# Faceplate_Display.net
KiCad netlist of a schematic drawn in Altium Designer
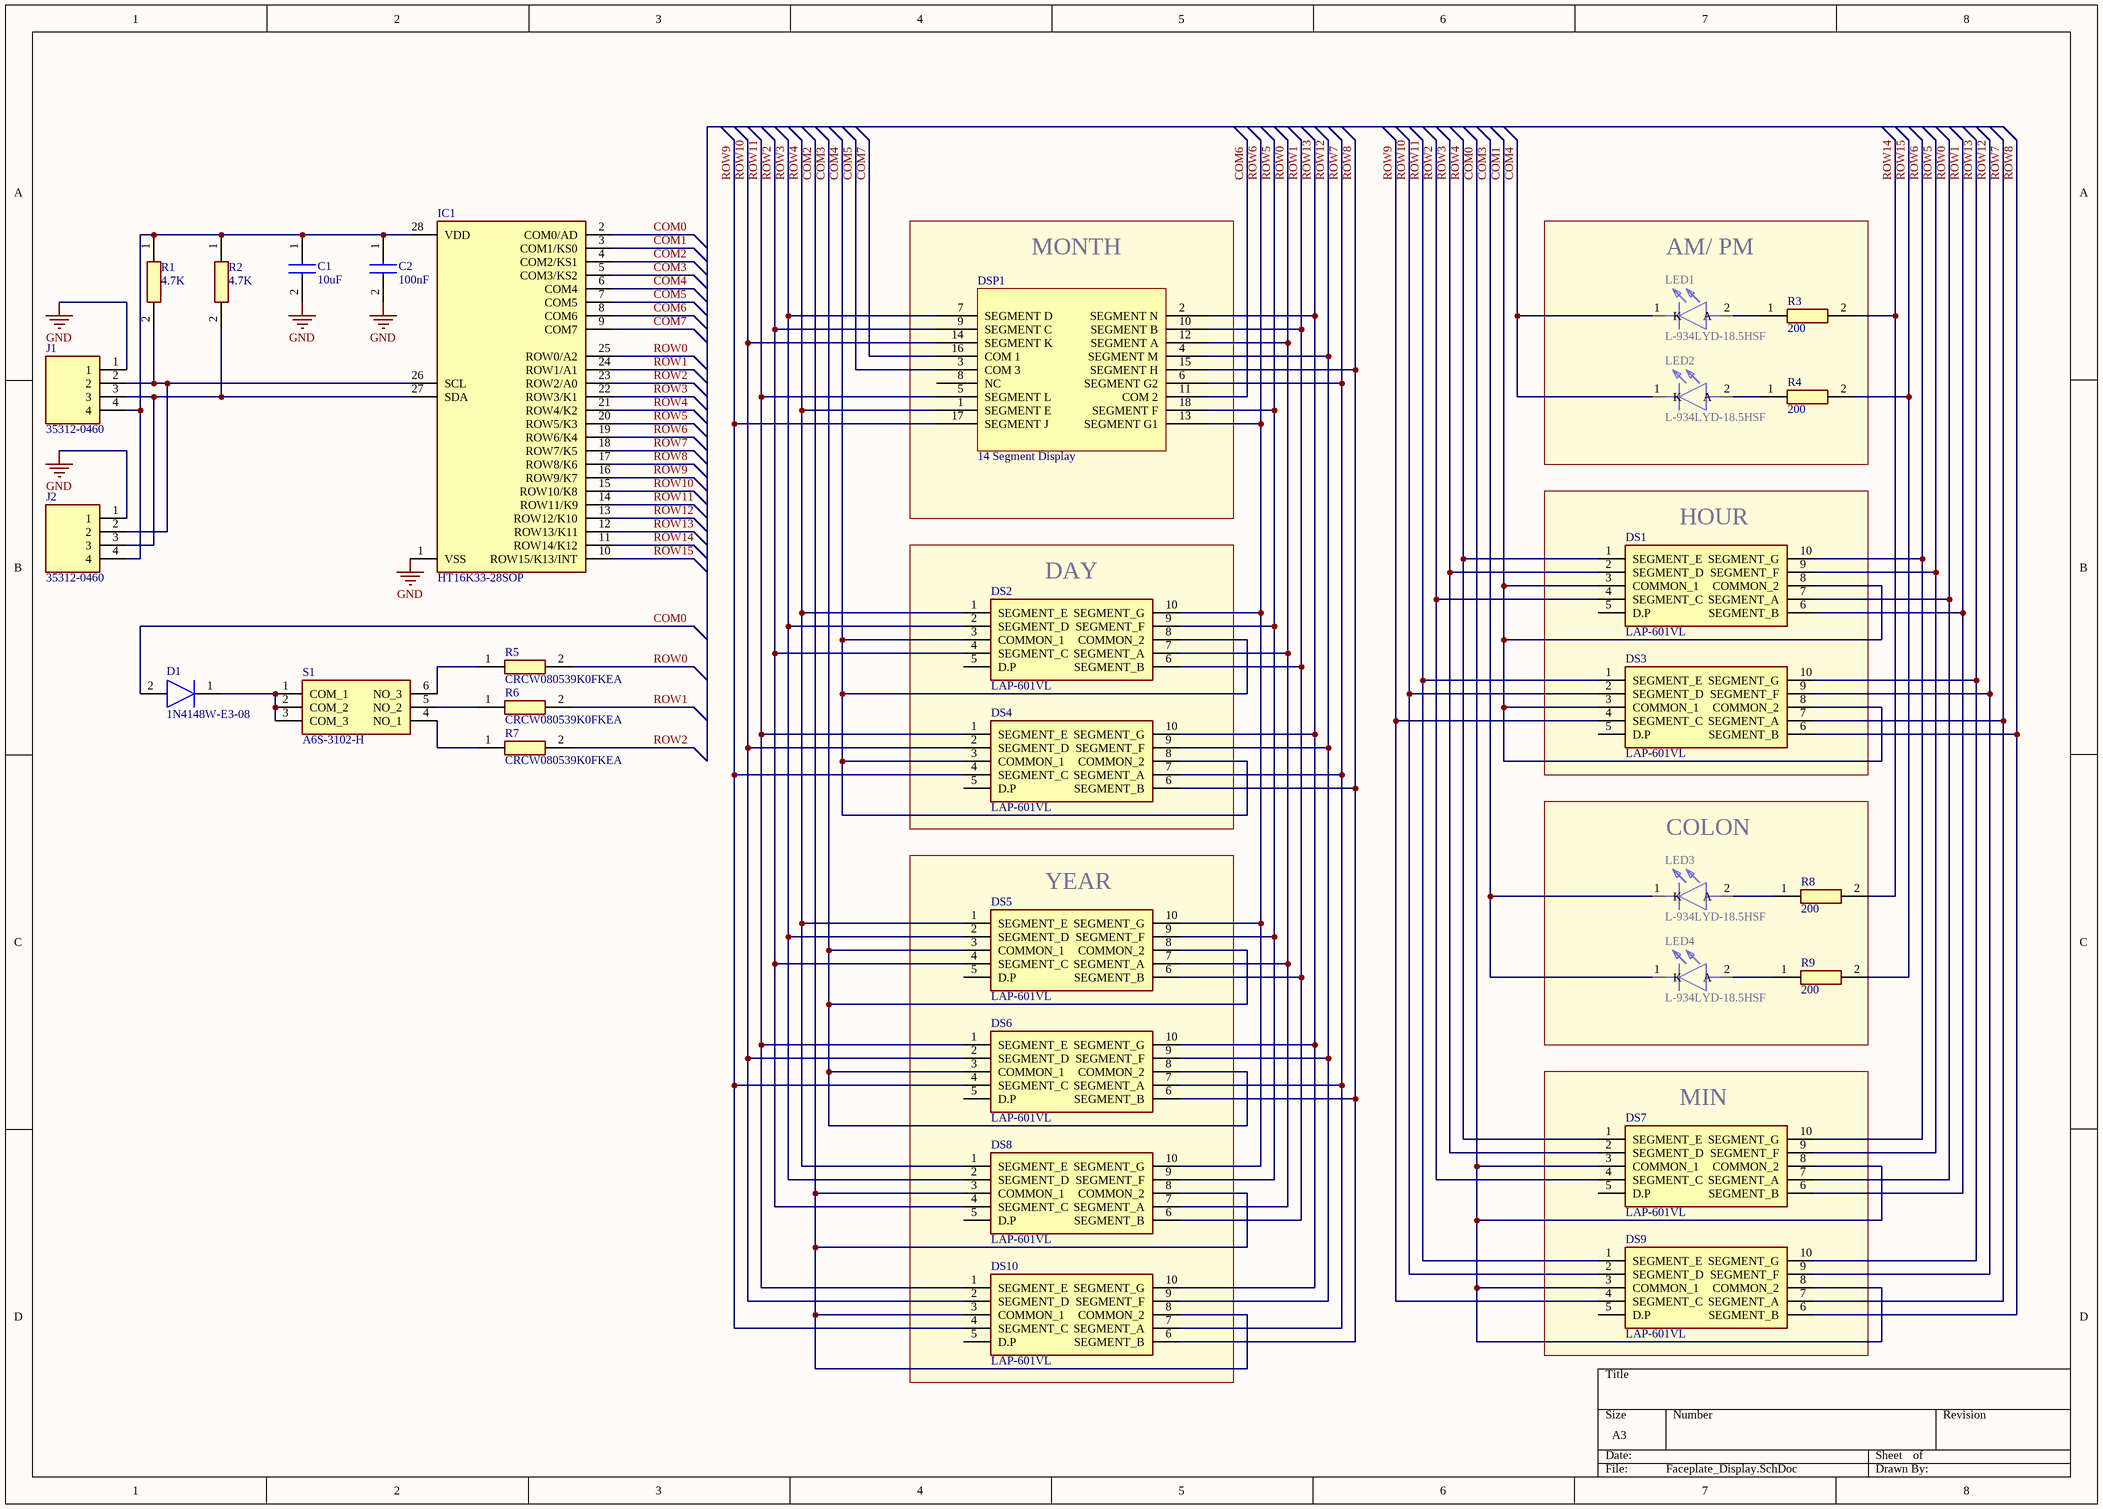
[diagram p0: Faceplate_Display.SchDoc]

(export (version "E")
  (design (tool "Eeschema 10.0.6"))
  (components
    (comp (ref "C1")
      (value "10uF")
      (footprint "SamacSys:CAPC2012X145N")
      (description "Capacitor")
      (fields
        (field (name "MANUFACTURER_PART_NUMBER") "VJ0805Y104KXAAT")
        (field (name "MOUSER PART NUMBER") "77-VJ0805Y104KXAAT")
      )
      (libsource (lib "*") (part "VJ0805Y104KXAAT"))
    )
    (comp (ref "C2")
      (value "100nF")
      (footprint "SamacSys:CAPC2012X88N")
      (description "Capacitor")
      (fields
        (field (name "MANUFACTURER_PART_NUMBER") "C0805C104K4RACTU")
        (field (name "MOUSER PART NUMBER") "80-C0805C104K4R")
      )
      (libsource (lib "*") (part "C0805C104K4RACTU"))
    )
    (comp (ref "D1")
      (value "1N4148W-E3-08")
      (footprint "SamacSys:SOD3716X135N")
      (description "Diode")
      (fields (field (name "MOUSER PART NUMBER") "78-1N4148W-E3-08"))
      (libsource (lib "*") (part "1N4148W-E3-08"))
    )
    (comp (ref "DS1")
      (value "LAP-601VL")
      (footprint "SamacSys:DIPS1524W50P254L1225H830Q10N")
      (description "Display")
      (fields (field (name "MOUSER PART NUMBER") "755-LAP-601VL"))
      (libsource (lib "SamacSys") (part "LAP-601VL"))
    )
    (comp (ref "DS2")
      (value "LAP-601VL")
      (footprint "DIPS1524W50P254L1225H830Q10N")
      (description "Display")
      (fields (field (name "MOUSER PART NUMBER") "755-LAP-601VL"))
      (libsource (lib "SamacSys") (part "LAP-601VL"))
    )
    (comp (ref "DS3")
      (value "LAP-601VL")
      (footprint "SamacSys:DIPS1524W50P254L1225H830Q10N")
      (description "Display")
      (fields (field (name "MOUSER PART NUMBER") "755-LAP-601VL"))
      (libsource (lib "SamacSys") (part "LAP-601VL"))
    )
    (comp (ref "DS4")
      (value "LAP-601VL")
      (footprint "DIPS1524W50P254L1225H830Q10N")
      (description "Display")
      (fields (field (name "MOUSER PART NUMBER") "755-LAP-601VL"))
      (libsource (lib "SamacSys") (part "LAP-601VL"))
    )
    (comp (ref "DS5")
      (value "LAP-601VL")
      (footprint "DIPS1524W50P254L1225H830Q10N")
      (description "Display")
      (fields (field (name "MOUSER PART NUMBER") "755-LAP-601VL"))
      (libsource (lib "SamacSys") (part "LAP-601VL"))
    )
    (comp (ref "DS6")
      (value "LAP-601VL")
      (footprint "SamacSys:DIPS1524W50P254L1225H830Q10N")
      (description "Display")
      (fields (field (name "MOUSER PART NUMBER") "755-LAP-601VL"))
      (libsource (lib "SamacSys") (part "LAP-601VL"))
    )
    (comp (ref "DS7")
      (value "LAP-601VL")
      (footprint "SamacSys:DIPS1524W50P254L1225H830Q10N")
      (description "Display")
      (fields (field (name "MOUSER PART NUMBER") "755-LAP-601VL"))
      (libsource (lib "SamacSys") (part "LAP-601VL"))
    )
    (comp (ref "DS8")
      (value "LAP-601VL")
      (footprint "SamacSys:DIPS1524W50P254L1225H830Q10N")
      (description "Display")
      (fields (field (name "MOUSER PART NUMBER") "755-LAP-601VL"))
      (libsource (lib "SamacSys") (part "LAP-601VL"))
    )
    (comp (ref "DS9")
      (value "LAP-601VL")
      (footprint "SamacSys:DIPS1524W50P254L1225H830Q10N")
      (description "Display")
      (fields (field (name "MOUSER PART NUMBER") "755-LAP-601VL"))
      (libsource (lib "SamacSys") (part "LAP-601VL"))
    )
    (comp (ref "DS10")
      (value "LAP-601VL")
      (footprint "SamacSys:DIPS1524W50P254L1225H830Q10N")
      (description "Display")
      (fields (field (name "MOUSER PART NUMBER") "755-LAP-601VL"))
      (libsource (lib "SamacSys") (part "LAP-601VL"))
    )
    (comp (ref "DSP1")
      (value "14 Segment Display")
      (footprint "14 Segment Display CS")
      (libsource (lib "3 Digit 14 Segment Component") (part "14 Segment Display"))
    )
    (comp (ref "IC1")
      (value "HT16K33-28SOP")
      (footprint "SamacSys:SOIC127P1031X264-28N")
      (description "Integrated Circuit")
      (libsource (lib "*") (part "HT16K33-28SOP"))
    )
    (comp (ref "J1")
      (value "35312-0460")
      (footprint "SamacSys:SHDR4W64P0X250_1X4_1246X650X700P")
      (description "Connector")
      (fields (field (name "MOUSER PART NUMBER") "538-35312-0460"))
      (libsource (lib "*") (part "35312-0460"))
    )
    (comp (ref "J2")
      (value "35312-0460")
      (footprint "SamacSys:SHDR4W64P0X250_1X4_1246X650X700P")
      (description "Connector")
      (fields (field (name "MOUSER PART NUMBER") "538-35312-0460"))
      (libsource (lib "*") (part "35312-0460"))
    )
    (comp (ref "LED1")
      (value "L-934LYD-18.5HSF")
      (footprint "SamacSys:L934LYD185HSF")
      (description "LED")
      (libsource (lib "*") (part "L-934LYD-18.5HSF"))
    )
    (comp (ref "LED2")
      (value "L-934LYD-18.5HSF")
      (footprint "SamacSys:L934LYD185HSF")
      (description "LED")
      (libsource (lib "*") (part "L-934LYD-18.5HSF"))
    )
    (comp (ref "LED3")
      (value "L-934LYD-18.5HSF")
      (footprint "SamacSys:L934LYD185HSF")
      (description "LED")
      (libsource (lib "*") (part "L-934LYD-18.5HSF"))
    )
    (comp (ref "LED4")
      (value "L-934LYD-18.5HSF")
      (footprint "SamacSys:L934LYD185HSF")
      (description "LED")
      (libsource (lib "*") (part "L-934LYD-18.5HSF"))
    )
    (comp (ref "R1")
      (value "4.7K")
      (footprint "SamacSys:RESC2012X50N")
      (description "Resistor")
      (fields
        (field (name "MANUFACTURER_PART_NUMBER") "CRCW08054K70FKEAHP")
        (field (name "MOUSER PART NUMBER") "71-CRCW08054K70FKEAH")
      )
      (libsource (lib "*") (part "CRCW08054K70FKEAHP"))
    )
    (comp (ref "R2")
      (value "4.7K")
      (footprint "SamacSys:RESC2012X50N")
      (description "Resistor")
      (fields
        (field (name "MANUFACTURER_PART_NUMBER") "CRCW08054K70FKEAHP")
        (field (name "MOUSER PART NUMBER") "71-CRCW08054K70FKEAH")
      )
      (libsource (lib "*") (part "CRCW08054K70FKEAHP"))
    )
    (comp (ref "R3")
      (value "200")
      (footprint "SamacSys:RESC2012X60N")
      (description "Resistor")
      (fields
        (field (name "MANUFACTURER_PART_NUMBER") "ERA-6AEB201V")
        (field (name "MOUSER PART NUMBER") "667-ERA-6AEB201V")
      )
      (libsource (lib "*") (part "ERA-6AEB201V"))
    )
    (comp (ref "R4")
      (value "200")
      (footprint "SamacSys:RESC2012X60N")
      (description "Resistor")
      (fields
        (field (name "MANUFACTURER_PART_NUMBER") "ERA-6AEB201V")
        (field (name "MOUSER PART NUMBER") "667-ERA-6AEB201V")
      )
      (libsource (lib "*") (part "ERA-6AEB201V"))
    )
    (comp (ref "R5")
      (value "CRCW080539K0FKEA")
      (footprint "SamacSys:RESC2012X50N")
      (description "Resistor")
      (fields (field (name "MOUSER PART NUMBER") "71-CRCW080539K0FKEA"))
      (libsource (lib "*") (part "CRCW080539K0FKEA"))
    )
    (comp (ref "R6")
      (value "CRCW080539K0FKEA")
      (footprint "SamacSys:RESC2012X50N")
      (description "Resistor")
      (fields (field (name "MOUSER PART NUMBER") "71-CRCW080539K0FKEA"))
      (libsource (lib "*") (part "CRCW080539K0FKEA"))
    )
    (comp (ref "R7")
      (value "CRCW080539K0FKEA")
      (footprint "SamacSys:RESC2012X50N")
      (description "Resistor")
      (fields (field (name "MOUSER PART NUMBER") "71-CRCW080539K0FKEA"))
      (libsource (lib "*") (part "CRCW080539K0FKEA"))
    )
    (comp (ref "R8")
      (value "200")
      (footprint "SamacSys:RESC2012X60N")
      (description "Resistor")
      (fields
        (field (name "MANUFACTURER_PART_NUMBER") "ERA-6AEB201V")
        (field (name "MOUSER PART NUMBER") "667-ERA-6AEB201V")
      )
      (libsource (lib "*") (part "ERA-6AEB201V"))
    )
    (comp (ref "R9")
      (value "200")
      (footprint "SamacSys:RESC2012X60N")
      (description "Resistor")
      (fields
        (field (name "MANUFACTURER_PART_NUMBER") "ERA-6AEB201V")
        (field (name "MOUSER PART NUMBER") "667-ERA-6AEB201V")
      )
      (libsource (lib "*") (part "ERA-6AEB201V"))
    )
    (comp (ref "S1")
      (value "A6S-3102-H")
      (footprint "SamacSys:SOP254P980X380-6N")
      (description "Switch")
      (fields (field (name "MOUSER PART NUMBER") "653-A6S-3102-H"))
      (libsource (lib "*") (part "A6S-3102-H"))
    )
  )
  (nets
    (net (code "1") (name "/COM0") (class "Default")
      (node (ref "D1") (pin "2") (pinfunction "A_2") (pintype "passive"))
      (node (ref "DS7") (pin "3") (pinfunction "COMMON_1_3") (pintype "passive"))
      (node (ref "DS7") (pin "8") (pinfunction "COMMON_2_8") (pintype "passive"))
      (node (ref "DS9") (pin "3") (pinfunction "COMMON_1_3") (pintype "passive"))
      (node (ref "DS9") (pin "8") (pinfunction "COMMON_2_8") (pintype "passive"))
      (node (ref "IC1") (pin "2") (pinfunction "COM0/AD_2") (pintype "passive"))
    )
    (net (code "2") (name "/COM1") (class "Default")
      (node (ref "DS1") (pin "3") (pinfunction "COMMON_1_3") (pintype "passive"))
      (node (ref "DS1") (pin "8") (pinfunction "COMMON_2_8") (pintype "passive"))
      (node (ref "DS3") (pin "3") (pinfunction "COMMON_1_3") (pintype "passive"))
      (node (ref "DS3") (pin "8") (pinfunction "COMMON_2_8") (pintype "passive"))
      (node (ref "IC1") (pin "3") (pinfunction "COM1/KS0_3") (pintype "passive"))
    )
    (net (code "3") (name "/COM2") (class "Default")
      (node (ref "DS10") (pin "3") (pinfunction "COMMON_1_3") (pintype "passive"))
      (node (ref "DS10") (pin "8") (pinfunction "COMMON_2_8") (pintype "passive"))
      (node (ref "DS8") (pin "3") (pinfunction "COMMON_1_3") (pintype "passive"))
      (node (ref "DS8") (pin "8") (pinfunction "COMMON_2_8") (pintype "passive"))
      (node (ref "IC1") (pin "4") (pinfunction "COM2/KS1_4") (pintype "passive"))
    )
    (net (code "4") (name "/COM3") (class "Default")
      (node (ref "DS5") (pin "3") (pinfunction "COMMON_1_3") (pintype "passive"))
      (node (ref "DS5") (pin "8") (pinfunction "COMMON_2_8") (pintype "passive"))
      (node (ref "DS6") (pin "3") (pinfunction "COMMON_1_3") (pintype "passive"))
      (node (ref "DS6") (pin "8") (pinfunction "COMMON_2_8") (pintype "passive"))
      (node (ref "IC1") (pin "5") (pinfunction "COM3/KS2_5") (pintype "passive"))
      (node (ref "LED3") (pin "1") (pinfunction "K_1") (pintype "passive"))
      (node (ref "LED4") (pin "1") (pinfunction "K_1") (pintype "passive"))
    )
    (net (code "5") (name "/COM4") (class "Default")
      (node (ref "DS2") (pin "3") (pinfunction "COMMON_1_3") (pintype "passive"))
      (node (ref "DS2") (pin "8") (pinfunction "COMMON_2_8") (pintype "passive"))
      (node (ref "DS4") (pin "3") (pinfunction "COMMON_1_3") (pintype "passive"))
      (node (ref "DS4") (pin "8") (pinfunction "COMMON_2_8") (pintype "passive"))
      (node (ref "IC1") (pin "6") (pinfunction "COM4_6") (pintype "passive"))
      (node (ref "LED1") (pin "1") (pinfunction "K_1") (pintype "passive"))
      (node (ref "LED2") (pin "1") (pinfunction "K_1") (pintype "passive"))
    )
    (net (code "6") (name "/COM5") (class "Default")
      (node (ref "DSP1") (pin "3") (pinfunction "COM_3_3") (pintype "passive"))
      (node (ref "IC1") (pin "7") (pinfunction "COM5_7") (pintype "passive"))
    )
    (net (code "7") (name "/COM6") (class "Default")
      (node (ref "DSP1") (pin "11") (pinfunction "COM_2_11") (pintype "passive"))
      (node (ref "IC1") (pin "8") (pinfunction "COM6_8") (pintype "passive"))
    )
    (net (code "8") (name "/COM7") (class "Default")
      (node (ref "DSP1") (pin "16") (pinfunction "COM_1_16") (pintype "passive"))
      (node (ref "IC1") (pin "9") (pinfunction "COM7_9") (pintype "passive"))
    )
    (net (code "9") (name "/ROW0") (class "Default")
      (node (ref "DS1") (pin "7") (pinfunction "SEGMENT_A_7") (pintype "passive"))
      (node (ref "DS2") (pin "7") (pinfunction "SEGMENT_A_7") (pintype "passive"))
      (node (ref "DS5") (pin "7") (pinfunction "SEGMENT_A_7") (pintype "passive"))
      (node (ref "DS7") (pin "7") (pinfunction "SEGMENT_A_7") (pintype "passive"))
      (node (ref "DS8") (pin "7") (pinfunction "SEGMENT_A_7") (pintype "passive"))
      (node (ref "DSP1") (pin "12") (pinfunction "SEGMENT_A_12") (pintype "passive"))
      (node (ref "IC1") (pin "25") (pinfunction "ROW0/A2_25") (pintype "passive"))
      (node (ref "R5") (pin "2") (pinfunction "2_2") (pintype "passive"))
    )
    (net (code "10") (name "/ROW1") (class "Default")
      (node (ref "DS1") (pin "6") (pinfunction "SEGMENT_B_6") (pintype "passive"))
      (node (ref "DS2") (pin "6") (pinfunction "SEGMENT_B_6") (pintype "passive"))
      (node (ref "DS5") (pin "6") (pinfunction "SEGMENT_B_6") (pintype "passive"))
      (node (ref "DS7") (pin "6") (pinfunction "SEGMENT_B_6") (pintype "passive"))
      (node (ref "DS8") (pin "6") (pinfunction "SEGMENT_B_6") (pintype "passive"))
      (node (ref "DSP1") (pin "10") (pinfunction "SEGMENT_B_10") (pintype "passive"))
      (node (ref "IC1") (pin "24") (pinfunction "ROW1/A1_24") (pintype "passive"))
      (node (ref "R6") (pin "2") (pinfunction "2_2") (pintype "passive"))
    )
    (net (code "11") (name "/ROW2") (class "Default")
      (node (ref "DS1") (pin "4") (pinfunction "SEGMENT_C_4") (pintype "passive"))
      (node (ref "DS2") (pin "4") (pinfunction "SEGMENT_C_4") (pintype "passive"))
      (node (ref "DS5") (pin "4") (pinfunction "SEGMENT_C_4") (pintype "passive"))
      (node (ref "DS7") (pin "4") (pinfunction "SEGMENT_C_4") (pintype "passive"))
      (node (ref "DS8") (pin "4") (pinfunction "SEGMENT_C_4") (pintype "passive"))
      (node (ref "DSP1") (pin "9") (pinfunction "SEGMENT_C_9") (pintype "passive"))
      (node (ref "IC1") (pin "23") (pinfunction "ROW2/A0_23") (pintype "passive"))
      (node (ref "R7") (pin "2") (pinfunction "2_2") (pintype "passive"))
    )
    (net (code "12") (name "/ROW3") (class "Default")
      (node (ref "DS1") (pin "2") (pinfunction "SEGMENT_D_2") (pintype "passive"))
      (node (ref "DS2") (pin "2") (pinfunction "SEGMENT_D_2") (pintype "passive"))
      (node (ref "DS5") (pin "2") (pinfunction "SEGMENT_D_2") (pintype "passive"))
      (node (ref "DS7") (pin "2") (pinfunction "SEGMENT_D_2") (pintype "passive"))
      (node (ref "DS8") (pin "2") (pinfunction "SEGMENT_D_2") (pintype "passive"))
      (node (ref "DSP1") (pin "7") (pinfunction "SEGMENT_D_7") (pintype "passive"))
      (node (ref "IC1") (pin "22") (pinfunction "ROW3/K1_22") (pintype "passive"))
    )
    (net (code "13") (name "/ROW4") (class "Default")
      (node (ref "DS1") (pin "1") (pinfunction "SEGMENT_E_1") (pintype "passive"))
      (node (ref "DS2") (pin "1") (pinfunction "SEGMENT_E_1") (pintype "passive"))
      (node (ref "DS5") (pin "1") (pinfunction "SEGMENT_E_1") (pintype "passive"))
      (node (ref "DS7") (pin "1") (pinfunction "SEGMENT_E_1") (pintype "passive"))
      (node (ref "DS8") (pin "1") (pinfunction "SEGMENT_E_1") (pintype "passive"))
      (node (ref "DSP1") (pin "1") (pinfunction "SEGMENT_E_1") (pintype "passive"))
      (node (ref "IC1") (pin "21") (pinfunction "ROW4/K2_21") (pintype "passive"))
    )
    (net (code "14") (name "/ROW5") (class "Default")
      (node (ref "DS1") (pin "9") (pinfunction "SEGMENT_F_9") (pintype "passive"))
      (node (ref "DS2") (pin "9") (pinfunction "SEGMENT_F_9") (pintype "passive"))
      (node (ref "DS5") (pin "9") (pinfunction "SEGMENT_F_9") (pintype "passive"))
      (node (ref "DS7") (pin "9") (pinfunction "SEGMENT_F_9") (pintype "passive"))
      (node (ref "DS8") (pin "9") (pinfunction "SEGMENT_F_9") (pintype "passive"))
      (node (ref "DSP1") (pin "18") (pinfunction "SEGMENT_F_18") (pintype "passive"))
      (node (ref "IC1") (pin "20") (pinfunction "ROW5/K3_20") (pintype "passive"))
    )
    (net (code "15") (name "/ROW6") (class "Default")
      (node (ref "DS1") (pin "10") (pinfunction "SEGMENT_G_10") (pintype "passive"))
      (node (ref "DS2") (pin "10") (pinfunction "SEGMENT_G_10") (pintype "passive"))
      (node (ref "DS5") (pin "10") (pinfunction "SEGMENT_G_10") (pintype "passive"))
      (node (ref "DS7") (pin "10") (pinfunction "SEGMENT_G_10") (pintype "passive"))
      (node (ref "DS8") (pin "10") (pinfunction "SEGMENT_G_10") (pintype "passive"))
      (node (ref "DSP1") (pin "13") (pinfunction "SEGMENT_G1_13") (pintype "passive"))
      (node (ref "IC1") (pin "19") (pinfunction "ROW6/K4_19") (pintype "passive"))
    )
    (net (code "16") (name "/ROW7") (class "Default")
      (node (ref "DS10") (pin "7") (pinfunction "SEGMENT_A_7") (pintype "passive"))
      (node (ref "DS3") (pin "7") (pinfunction "SEGMENT_A_7") (pintype "passive"))
      (node (ref "DS4") (pin "7") (pinfunction "SEGMENT_A_7") (pintype "passive"))
      (node (ref "DS6") (pin "7") (pinfunction "SEGMENT_A_7") (pintype "passive"))
      (node (ref "DS9") (pin "7") (pinfunction "SEGMENT_A_7") (pintype "passive"))
      (node (ref "DSP1") (pin "6") (pinfunction "SEGMENT_G2_6") (pintype "passive"))
      (node (ref "IC1") (pin "18") (pinfunction "ROW7/K5_18") (pintype "passive"))
    )
    (net (code "17") (name "/ROW8") (class "Default")
      (node (ref "DS10") (pin "6") (pinfunction "SEGMENT_B_6") (pintype "passive"))
      (node (ref "DS3") (pin "6") (pinfunction "SEGMENT_B_6") (pintype "passive"))
      (node (ref "DS4") (pin "6") (pinfunction "SEGMENT_B_6") (pintype "passive"))
      (node (ref "DS6") (pin "6") (pinfunction "SEGMENT_B_6") (pintype "passive"))
      (node (ref "DS9") (pin "6") (pinfunction "SEGMENT_B_6") (pintype "passive"))
      (node (ref "DSP1") (pin "15") (pinfunction "SEGMENT_H_15") (pintype "passive"))
      (node (ref "IC1") (pin "17") (pinfunction "ROW8/K6_17") (pintype "passive"))
    )
    (net (code "18") (name "/ROW9") (class "Default")
      (node (ref "DS10") (pin "4") (pinfunction "SEGMENT_C_4") (pintype "passive"))
      (node (ref "DS3") (pin "4") (pinfunction "SEGMENT_C_4") (pintype "passive"))
      (node (ref "DS4") (pin "4") (pinfunction "SEGMENT_C_4") (pintype "passive"))
      (node (ref "DS6") (pin "4") (pinfunction "SEGMENT_C_4") (pintype "passive"))
      (node (ref "DS9") (pin "4") (pinfunction "SEGMENT_C_4") (pintype "passive"))
      (node (ref "DSP1") (pin "17") (pinfunction "SEGMENT_J_17") (pintype "passive"))
      (node (ref "IC1") (pin "16") (pinfunction "ROW9/K7_16") (pintype "passive"))
    )
    (net (code "19") (name "/ROW10") (class "Default")
      (node (ref "DS10") (pin "2") (pinfunction "SEGMENT_D_2") (pintype "passive"))
      (node (ref "DS3") (pin "2") (pinfunction "SEGMENT_D_2") (pintype "passive"))
      (node (ref "DS4") (pin "2") (pinfunction "SEGMENT_D_2") (pintype "passive"))
      (node (ref "DS6") (pin "2") (pinfunction "SEGMENT_D_2") (pintype "passive"))
      (node (ref "DS9") (pin "2") (pinfunction "SEGMENT_D_2") (pintype "passive"))
      (node (ref "DSP1") (pin "14") (pinfunction "SEGMENT_K_14") (pintype "passive"))
      (node (ref "IC1") (pin "15") (pinfunction "ROW10/K8_15") (pintype "passive"))
    )
    (net (code "20") (name "/ROW11") (class "Default")
      (node (ref "DS10") (pin "1") (pinfunction "SEGMENT_E_1") (pintype "passive"))
      (node (ref "DS3") (pin "1") (pinfunction "SEGMENT_E_1") (pintype "passive"))
      (node (ref "DS4") (pin "1") (pinfunction "SEGMENT_E_1") (pintype "passive"))
      (node (ref "DS6") (pin "1") (pinfunction "SEGMENT_E_1") (pintype "passive"))
      (node (ref "DS9") (pin "1") (pinfunction "SEGMENT_E_1") (pintype "passive"))
      (node (ref "DSP1") (pin "5") (pinfunction "SEGMENT_L_5") (pintype "passive"))
      (node (ref "IC1") (pin "14") (pinfunction "ROW11/K9_14") (pintype "passive"))
    )
    (net (code "21") (name "/ROW12") (class "Default")
      (node (ref "DS10") (pin "9") (pinfunction "SEGMENT_F_9") (pintype "passive"))
      (node (ref "DS3") (pin "9") (pinfunction "SEGMENT_F_9") (pintype "passive"))
      (node (ref "DS4") (pin "9") (pinfunction "SEGMENT_F_9") (pintype "passive"))
      (node (ref "DS6") (pin "9") (pinfunction "SEGMENT_F_9") (pintype "passive"))
      (node (ref "DS9") (pin "9") (pinfunction "SEGMENT_F_9") (pintype "passive"))
      (node (ref "DSP1") (pin "4") (pinfunction "SEGMENT_M_4") (pintype "passive"))
      (node (ref "IC1") (pin "13") (pinfunction "ROW12/K10_13") (pintype "passive"))
    )
    (net (code "22") (name "/ROW13") (class "Default")
      (node (ref "DS10") (pin "10") (pinfunction "SEGMENT_G_10") (pintype "passive"))
      (node (ref "DS3") (pin "10") (pinfunction "SEGMENT_G_10") (pintype "passive"))
      (node (ref "DS4") (pin "10") (pinfunction "SEGMENT_G_10") (pintype "passive"))
      (node (ref "DS6") (pin "10") (pinfunction "SEGMENT_G_10") (pintype "passive"))
      (node (ref "DS9") (pin "10") (pinfunction "SEGMENT_G_10") (pintype "passive"))
      (node (ref "DSP1") (pin "2") (pinfunction "SEGMENT_N_2") (pintype "passive"))
      (node (ref "IC1") (pin "12") (pinfunction "ROW13/K11_12") (pintype "passive"))
    )
    (net (code "23") (name "/ROW14") (class "Default")
      (node (ref "IC1") (pin "11") (pinfunction "ROW14/K12_11") (pintype "passive"))
      (node (ref "R3") (pin "2") (pinfunction "2_2") (pintype "passive"))
      (node (ref "R8") (pin "2") (pinfunction "2_2") (pintype "passive"))
    )
    (net (code "24") (name "/ROW15") (class "Default")
      (node (ref "IC1") (pin "10") (pinfunction "ROW15/K13/INT_10") (pintype "passive"))
      (node (ref "R4") (pin "2") (pinfunction "2_2") (pintype "passive"))
      (node (ref "R9") (pin "2") (pinfunction "2_2") (pintype "passive"))
    )
    (net (code "25") (name "GND") (class "Default")
      (node (ref "C1") (pin "2") (pinfunction "2_2") (pintype "passive"))
      (node (ref "C2") (pin "2") (pinfunction "2_2") (pintype "passive"))
      (node (ref "IC1") (pin "1") (pinfunction "VSS_1") (pintype "passive"))
      (node (ref "J1") (pin "1") (pinfunction "1_1") (pintype "passive"))
      (node (ref "J2") (pin "1") (pinfunction "1_1") (pintype "passive"))
    )
    (net (code "26") (name "Net-(D1-K)") (class "Default")
      (node (ref "D1") (pin "1") (pinfunction "K_1") (pintype "passive"))
      (node (ref "S1") (pin "1") (pinfunction "COM_1_1") (pintype "passive"))
      (node (ref "S1") (pin "2") (pinfunction "COM_2_2") (pintype "passive"))
      (node (ref "S1") (pin "3") (pinfunction "COM_3_3") (pintype "passive"))
    )
    (net (code "27") (name "Net-(IC1-SCL)") (class "Default")
      (node (ref "IC1") (pin "26") (pinfunction "SCL_26") (pintype "passive"))
      (node (ref "J1") (pin "2") (pinfunction "2_2") (pintype "passive"))
      (node (ref "J2") (pin "2") (pinfunction "2_2") (pintype "passive"))
      (node (ref "R1") (pin "2") (pinfunction "2_2") (pintype "passive"))
    )
    (net (code "28") (name "Net-(IC1-SDA)") (class "Default")
      (node (ref "IC1") (pin "27") (pinfunction "SDA_27") (pintype "passive"))
      (node (ref "J1") (pin "3") (pinfunction "3_3") (pintype "passive"))
      (node (ref "J2") (pin "3") (pinfunction "3_3") (pintype "passive"))
      (node (ref "R2") (pin "2") (pinfunction "2_2") (pintype "passive"))
    )
    (net (code "29") (name "Net-(IC1-VDD)") (class "Default")
      (node (ref "C1") (pin "1") (pinfunction "1_1") (pintype "passive"))
      (node (ref "C2") (pin "1") (pinfunction "1_1") (pintype "passive"))
      (node (ref "IC1") (pin "28") (pinfunction "VDD_28") (pintype "passive"))
      (node (ref "J1") (pin "4") (pinfunction "4_4") (pintype "passive"))
      (node (ref "J2") (pin "4") (pinfunction "4_4") (pintype "passive"))
      (node (ref "R1") (pin "1") (pinfunction "1_1") (pintype "passive"))
      (node (ref "R2") (pin "1") (pinfunction "1_1") (pintype "passive"))
    )
    (net (code "30") (name "Net-(LED1-A)") (class "Default")
      (node (ref "LED1") (pin "2") (pinfunction "A_2") (pintype "passive"))
      (node (ref "R3") (pin "1") (pinfunction "1_1") (pintype "passive"))
    )
    (net (code "31") (name "Net-(LED2-A)") (class "Default")
      (node (ref "LED2") (pin "2") (pinfunction "A_2") (pintype "passive"))
      (node (ref "R4") (pin "1") (pinfunction "1_1") (pintype "passive"))
    )
    (net (code "32") (name "Net-(LED3-A)") (class "Default")
      (node (ref "LED3") (pin "2") (pinfunction "A_2") (pintype "passive"))
      (node (ref "R8") (pin "1") (pinfunction "1_1") (pintype "passive"))
    )
    (net (code "33") (name "Net-(LED4-A)") (class "Default")
      (node (ref "LED4") (pin "2") (pinfunction "A_2") (pintype "passive"))
      (node (ref "R9") (pin "1") (pinfunction "1_1") (pintype "passive"))
    )
    (net (code "34") (name "Net-(S1-NO_1)") (class "Default")
      (node (ref "R7") (pin "1") (pinfunction "1_1") (pintype "passive"))
      (node (ref "S1") (pin "4") (pinfunction "NO_1_4") (pintype "passive"))
    )
    (net (code "35") (name "Net-(S1-NO_2)") (class "Default")
      (node (ref "R6") (pin "1") (pinfunction "1_1") (pintype "passive"))
      (node (ref "S1") (pin "5") (pinfunction "NO_2_5") (pintype "passive"))
    )
    (net (code "36") (name "Net-(S1-NO_3)") (class "Default")
      (node (ref "R5") (pin "1") (pinfunction "1_1") (pintype "passive"))
      (node (ref "S1") (pin "6") (pinfunction "NO_3_6") (pintype "passive"))
    )
    (net (code "37") (name "unconnected-(DS1-D.P-Pad5)") (class "Default")
      (node (ref "DS1") (pin "5") (pinfunction "D.P_5") (pintype "passive"))
    )
    (net (code "38") (name "unconnected-(DS2-D.P-Pad5)") (class "Default")
      (node (ref "DS2") (pin "5") (pinfunction "D.P_5") (pintype "passive"))
    )
    (net (code "39") (name "unconnected-(DS3-D.P-Pad5)") (class "Default")
      (node (ref "DS3") (pin "5") (pinfunction "D.P_5") (pintype "passive"))
    )
    (net (code "40") (name "unconnected-(DS4-D.P-Pad5)") (class "Default")
      (node (ref "DS4") (pin "5") (pinfunction "D.P_5") (pintype "passive"))
    )
    (net (code "41") (name "unconnected-(DS5-D.P-Pad5)") (class "Default")
      (node (ref "DS5") (pin "5") (pinfunction "D.P_5") (pintype "passive"))
    )
    (net (code "42") (name "unconnected-(DS6-D.P-Pad5)") (class "Default")
      (node (ref "DS6") (pin "5") (pinfunction "D.P_5") (pintype "passive"))
    )
    (net (code "43") (name "unconnected-(DS7-D.P-Pad5)") (class "Default")
      (node (ref "DS7") (pin "5") (pinfunction "D.P_5") (pintype "passive"))
    )
    (net (code "44") (name "unconnected-(DS8-D.P-Pad5)") (class "Default")
      (node (ref "DS8") (pin "5") (pinfunction "D.P_5") (pintype "passive"))
    )
    (net (code "45") (name "unconnected-(DS9-D.P-Pad5)") (class "Default")
      (node (ref "DS9") (pin "5") (pinfunction "D.P_5") (pintype "passive"))
    )
    (net (code "46") (name "unconnected-(DS10-D.P-Pad5)") (class "Default")
      (node (ref "DS10") (pin "5") (pinfunction "D.P_5") (pintype "passive"))
    )
    (net (code "47") (name "unconnected-(DSP1-NC-Pad8)") (class "Default")
      (node (ref "DSP1") (pin "8") (pinfunction "NC_8") (pintype "passive"))
    )
  )
)
